# EPS_MPPT_Y_EMI-Filter_Solar-Panels.net
KiCad netlist of a schematic drawn in Altium Designer
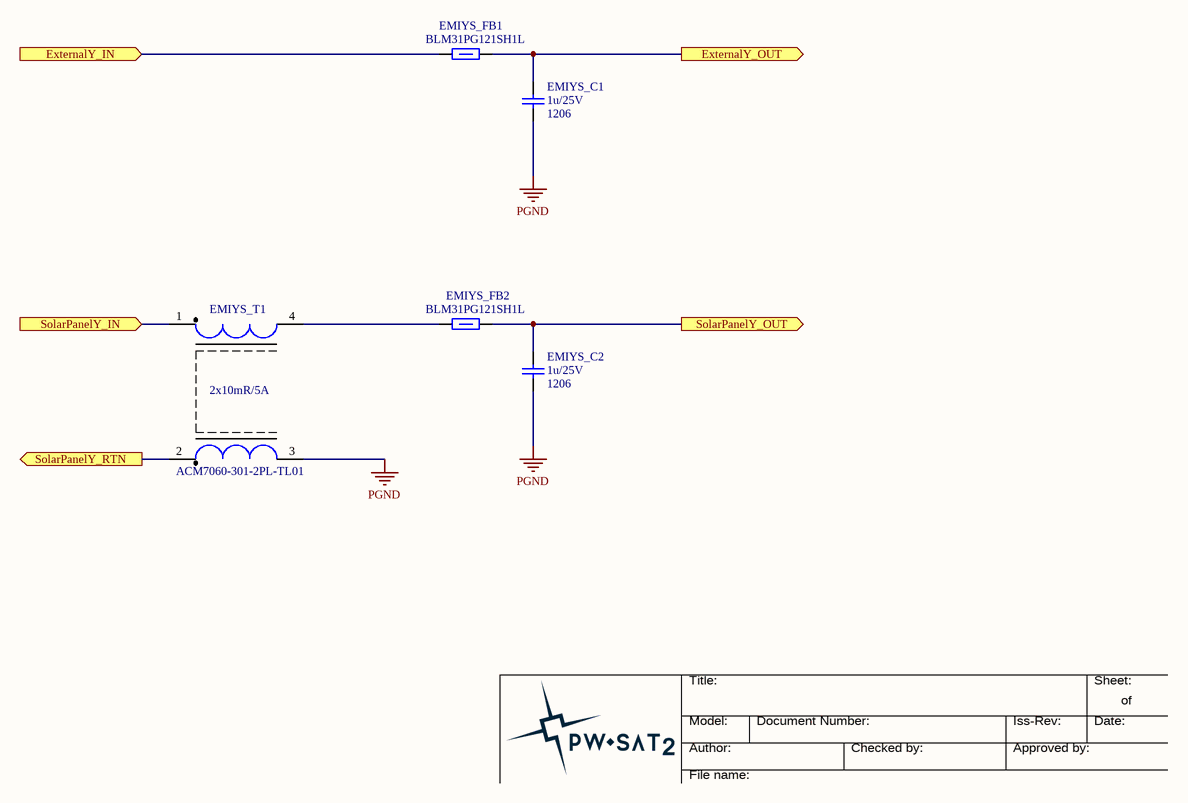
[diagram p0: EPS_MPPT_Y_EMI-Filter_Solar-Panels.SchDoc]

(export (version "E")
  (design (tool "Eeschema 10.0.6"))
  (components
    (comp (ref "EMIYS_C1")
      (value "1u/25V")
      (footprint "SMD_Capacitor_1206")
      (description "Ceramic Cap Kemet COTS 1u/25V X7R 1206")
      (fields
        (field (name "MANUFACTURERPARTNUMBER") "C1206T105K3RALTU")
        (field (name "MANUFACTURER") "Kemet")
        (field (name "PACKAGE") "1206")
      )
      (libsource (lib "capacitors") (part "Cer_C1206T105K3RALTU"))
    )
    (comp (ref "EMIYS_C2")
      (value "1u/25V")
      (footprint "SMD_Capacitor_1206")
      (description "Ceramic Cap Kemet COTS 1u/25V X7R 1206")
      (fields
        (field (name "MANUFACTURERPARTNUMBER") "C1206T105K3RALTU")
        (field (name "MANUFACTURER") "Kemet")
        (field (name "PACKAGE") "1206")
      )
      (libsource (lib "capacitors") (part "Cer_C1206T105K3RALTU"))
    )
    (comp (ref "EMIYS_FB1")
      (value "120R/100MHz")
      (footprint "SMD_FerriteBead_1206")
      (description "Ferrite bead, 1206, 0.02HM, 3.5A.")
      (fields (field (name "MANUFACTURER") "Murata") (field (name "MANUFACTURERPARTNUMBER") "BLM31PG121SH1L"))
      (libsource (lib "inductors") (part "BLM31PG121SH1L"))
    )
    (comp (ref "EMIYS_FB2")
      (value "120R/100MHz")
      (footprint "SMD_FerriteBead_1206")
      (description "Ferrite bead, 1206, 0.02HM, 3.5A.")
      (fields (field (name "MANUFACTURER") "Murata") (field (name "MANUFACTURERPARTNUMBER") "BLM31PG121SH1L"))
      (libsource (lib "inductors") (part "BLM31PG121SH1L"))
    )
    (comp (ref "EMIYS_T1")
      (value "2x10mR/5A")
      (footprint "TDK_ACM7060")
      (description "TDK ACM7060-301 Common Mode Choke")
      (fields
        (field (name "MANUFACTURER") "TDK")
        (field (name "MANUFACTURERPARTNUMBER") "ACM7060-301-2PL-TL01")
      )
      (libsource (lib "inductors") (part "ACM7060-301-2PL-TL01"))
    )
  )
  (nets
    (net (code "1") (name "/ExternalY_IN") (class "Default")
      (node (ref "EMIYS_FB1") (pin "2") (pinfunction "2_2") (pintype "passive"))
    )
    (net (code "2") (name "/ExternalY_OUT") (class "Default")
      (node (ref "EMIYS_C1") (pin "1") (pinfunction "1_1") (pintype "passive"))
      (node (ref "EMIYS_FB1") (pin "1") (pinfunction "1_1") (pintype "passive"))
    )
    (net (code "3") (name "/SolarPanelY_IN") (class "Default")
      (node (ref "EMIYS_T1") (pin "1") (pinfunction "1_1") (pintype "passive"))
    )
    (net (code "4") (name "/SolarPanelY_OUT") (class "Default")
      (node (ref "EMIYS_C2") (pin "1") (pinfunction "1_1") (pintype "passive"))
      (node (ref "EMIYS_FB2") (pin "1") (pinfunction "1_1") (pintype "passive"))
    )
    (net (code "5") (name "/SolarPanelY_RTN") (class "Default")
      (node (ref "EMIYS_T1") (pin "2") (pinfunction "2_2") (pintype "passive"))
    )
    (net (code "6") (name "Net-(EMIYS_FB2-Pad2)") (class "Default")
      (node (ref "EMIYS_FB2") (pin "2") (pinfunction "2_2") (pintype "passive"))
      (node (ref "EMIYS_T1") (pin "4") (pinfunction "4_4") (pintype "passive"))
    )
    (net (code "7") (name "PGND") (class "Default")
      (node (ref "EMIYS_C1") (pin "2") (pinfunction "2_2") (pintype "passive"))
      (node (ref "EMIYS_C2") (pin "2") (pinfunction "2_2") (pintype "passive"))
      (node (ref "EMIYS_T1") (pin "3") (pinfunction "3_3") (pintype "passive"))
    )
  )
)
